# Sheet2.net
KiCad netlist of a schematic drawn in Altium Designer
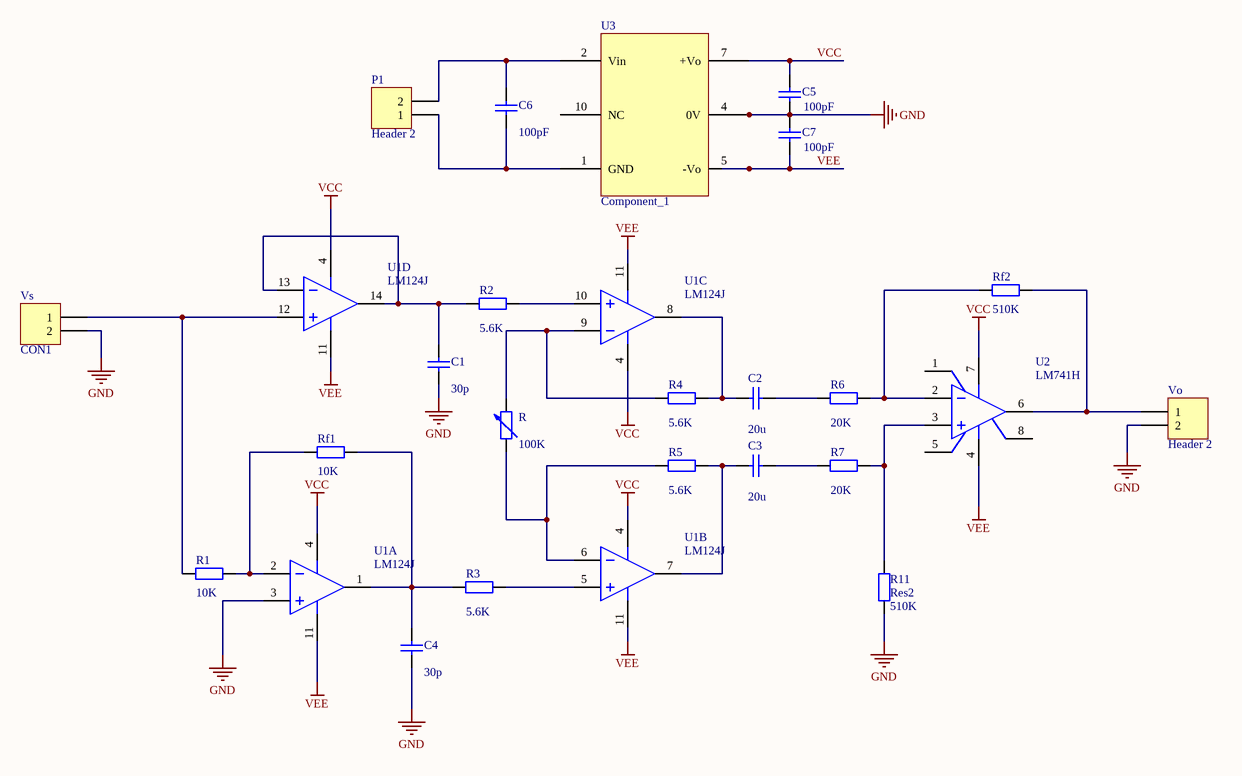
[diagram p0: Sheet2.SchDoc]

(export (version "E")
  (design (tool "Eeschema 10.0.6"))
  (components
    (comp (ref "C1")
      (value "30p")
      (footprint "RAD-0.3")
      (description "Capacitor")
      (fields (field (name "Comment") "Cap") (field (name "PUBLISHER") "Altium Limited"))
      (libsource (lib "Miscellaneous Devices") (part "Cap"))
    )
    (comp (ref "C2")
      (value "20u")
      (footprint "RAD-0.3")
      (description "Capacitor")
      (fields (field (name "Comment") "Cap") (field (name "PUBLISHER") "Altium Limited"))
      (libsource (lib "Miscellaneous Devices") (part "Cap"))
    )
    (comp (ref "C3")
      (value "20u")
      (footprint "RAD-0.3")
      (description "Capacitor")
      (fields (field (name "Comment") "Cap") (field (name "PUBLISHER") "Altium Limited"))
      (libsource (lib "Miscellaneous Devices") (part "Cap"))
    )
    (comp (ref "C4")
      (value "30p")
      (footprint "RAD-0.3")
      (description "Capacitor")
      (fields (field (name "Comment") "Cap") (field (name "PUBLISHER") "Altium Limited"))
      (libsource (lib "Miscellaneous Devices") (part "Cap"))
    )
    (comp (ref "C5")
      (value "100pF")
      (footprint "RAD-0.3")
      (description "Capacitor")
      (fields (field (name "Comment") "Cap") (field (name "PUBLISHER") "Altium Limited"))
      (libsource (lib "Miscellaneous Devices") (part "Cap"))
    )
    (comp (ref "C6")
      (value "100pF")
      (footprint "RAD-0.3")
      (description "Capacitor")
      (fields (field (name "Comment") "Cap") (field (name "PUBLISHER") "Altium Limited"))
      (libsource (lib "Miscellaneous Devices") (part "Cap"))
    )
    (comp (ref "C7")
      (value "100pF")
      (footprint "RAD-0.3")
      (description "Capacitor")
      (fields (field (name "Comment") "Cap") (field (name "PUBLISHER") "Altium Limited"))
      (libsource (lib "Miscellaneous Devices") (part "Cap"))
    )
    (comp (ref "P1")
      (value "Header 2")
      (footprint "HDR1X2")
      (description "Header, 2-Pin")
      (fields (field (name "PUBLISHER") "Altium Limited"))
      (libsource (lib "") (part "Header 2_2"))
    )
    (comp (ref "R")
      (value "100K")
      (footprint "AXIAL-0.6")
      (description "Variable Resistor")
      (fields (field (name "Comment") "Res Adj2") (field (name "PUBLISHER") "Altium Limited"))
      (libsource (lib "Miscellaneous Devices") (part "Res Adj2"))
    )
    (comp (ref "R1")
      (value "10K")
      (footprint "AXIAL-0.4")
      (description "Resistor")
      (fields (field (name "Comment") "Res2") (field (name "PUBLISHER") "Altium Limited"))
      (libsource (lib "") (part "Res2_1"))
    )
    (comp (ref "R2")
      (value "5.6K")
      (footprint "AXIAL-0.4")
      (description "Resistor")
      (fields (field (name "Comment") "Res2") (field (name "PUBLISHER") "Altium Limited"))
      (libsource (lib "") (part "Res2_1"))
    )
    (comp (ref "R3")
      (value "5.6K")
      (footprint "AXIAL-0.4")
      (description "Resistor")
      (fields (field (name "Comment") "Res2") (field (name "PUBLISHER") "Altium Limited"))
      (libsource (lib "") (part "Res2_1"))
    )
    (comp (ref "R4")
      (value "5.6K")
      (footprint "AXIAL-0.4")
      (description "Resistor")
      (fields (field (name "Comment") "Res2") (field (name "PUBLISHER") "Altium Limited"))
      (libsource (lib "") (part "Res2_1"))
    )
    (comp (ref "R5")
      (value "5.6K")
      (footprint "AXIAL-0.4")
      (description "Resistor")
      (fields (field (name "Comment") "Res2") (field (name "PUBLISHER") "Altium Limited"))
      (libsource (lib "") (part "Res2_1"))
    )
    (comp (ref "R6")
      (value "20K")
      (footprint "AXIAL-0.4")
      (description "Resistor")
      (fields (field (name "Comment") "Res2") (field (name "PUBLISHER") "Altium Limited"))
      (libsource (lib "") (part "Res2_1"))
    )
    (comp (ref "R7")
      (value "20K")
      (footprint "AXIAL-0.4")
      (description "Resistor")
      (fields (field (name "Comment") "Res2") (field (name "PUBLISHER") "Altium Limited"))
      (libsource (lib "") (part "Res2_1"))
    )
    (comp (ref "R11")
      (value "Res2")
      (footprint "AXIAL-0.4")
      (description "Resistor")
      (fields (field (name "ALTIUM_VALUE") "510K") (field (name "PUBLISHER") "Altium Limited"))
      (libsource (lib "") (part "Res2_2"))
    )
    (comp (ref "Rf1")
      (value "10K")
      (footprint "AXIAL-0.4")
      (description "Resistor")
      (fields (field (name "Comment") "Res2") (field (name "PUBLISHER") "Altium Limited"))
      (libsource (lib "") (part "Res2_1"))
    )
    (comp (ref "Rf2")
      (value "510K")
      (footprint "AXIAL-0.4")
      (description "Resistor")
      (fields (field (name "Comment") "Res2") (field (name "PUBLISHER") "Altium Limited"))
      (libsource (lib "Miscellaneous Devices") (part "Res2"))
    )
    (comp (ref "U1")
      (value "LM124J")
      (footprint "J14A")
      (description "Low Power Quad Operational Amplifier, 14-pin CerDIP")
      (fields
        (field (name "MANUFACTURER") "National Semiconductor")
        (field (name "PUBLISHER") "Altium Limited")
      )
      (libsource (lib "NSC Amplifier") (part "LM124J"))
    )
    (comp (ref "U2")
      (value "LM741H")
      (footprint "H08C")
      (description "Operational Amplifier, 8-pin TO-99")
      (fields
        (field (name "MANUFACTURER") "National Semiconductor")
        (field (name "PUBLISHER") "Altium Limited")
      )
      (libsource (lib "NSC Amplifier") (part "LM741H"))
    )
    (comp (ref "U3")
      (value "Component_1")
      (footprint "PCBComponent_1")
      (libsource (lib "Schlib1") (part "Component_1"))
    )
    (comp (ref "Vo")
      (value "Header 2")
      (footprint "HDR1X2")
      (description "Header, 2-Pin")
      (fields (field (name "PUBLISHER") "Altium Limited"))
      (libsource (lib "") (part "Header 2_1"))
    )
    (comp (ref "Vs")
      (value "CON1")
      (footprint "HDR1X2")
      (description "Header, 2-Pin")
      (fields (field (name "PUBLISHER") "Altium Limited"))
      (libsource (lib "Miscellaneous Connectors") (part "Header 2"))
    )
  )
  (nets
    (net (code "1") (name "GND") (class "Default")
      (node (ref "C1") (pin "1") (pinfunction "1_1") (pintype "passive"))
      (node (ref "C4") (pin "1") (pinfunction "1_1") (pintype "passive"))
      (node (ref "C5") (pin "1") (pinfunction "1_1") (pintype "passive"))
      (node (ref "C7") (pin "2") (pinfunction "2_2") (pintype "passive"))
      (node (ref "R11") (pin "1") (pinfunction "1_1") (pintype "passive"))
      (node (ref "U1") (pin "3") (pinfunction "IN1+_3") (pintype "passive"))
      (node (ref "U3") (pin "4") (pinfunction "0V_4") (pintype "passive"))
      (node (ref "Vo") (pin "2") (pinfunction "2_2") (pintype "passive"))
      (node (ref "Vs") (pin "2") (pinfunction "2_2") (pintype "passive"))
    )
    (net (code "2") (name "Net-(C2-Pad2)") (class "Default")
      (node (ref "C2") (pin "2") (pinfunction "2_2") (pintype "passive"))
      (node (ref "R6") (pin "1") (pinfunction "1_1") (pintype "passive"))
    )
    (net (code "3") (name "Net-(C3-Pad2)") (class "Default")
      (node (ref "C3") (pin "2") (pinfunction "2_2") (pintype "passive"))
      (node (ref "R7") (pin "1") (pinfunction "1_1") (pintype "passive"))
    )
    (net (code "4") (name "Net-(U1A-IN1-)") (class "Default")
      (node (ref "R1") (pin "2") (pinfunction "2_2") (pintype "passive"))
      (node (ref "Rf1") (pin "1") (pinfunction "1_1") (pintype "passive"))
      (node (ref "U1") (pin "2") (pinfunction "IN1-_2") (pintype "passive"))
    )
    (net (code "5") (name "Net-(U1A-OUT1)") (class "Default")
      (node (ref "C4") (pin "2") (pinfunction "2_2") (pintype "passive"))
      (node (ref "R3") (pin "1") (pinfunction "1_1") (pintype "passive"))
      (node (ref "Rf1") (pin "2") (pinfunction "2_2") (pintype "passive"))
      (node (ref "U1") (pin "1") (pinfunction "OUT1_1") (pintype "passive"))
    )
    (net (code "6") (name "Net-(U1B-IN2+)") (class "Default")
      (node (ref "R3") (pin "2") (pinfunction "2_2") (pintype "passive"))
      (node (ref "U1") (pin "5") (pinfunction "IN2+_5") (pintype "input"))
    )
    (net (code "7") (name "Net-(U1B-IN2-)") (class "Default")
      (node (ref "R") (pin "1") (pinfunction "1_1") (pintype "passive"))
      (node (ref "R5") (pin "1") (pinfunction "1_1") (pintype "passive"))
      (node (ref "U1") (pin "6") (pinfunction "IN2-_6") (pintype "input"))
    )
    (net (code "8") (name "Net-(U1B-OUT2)") (class "Default")
      (node (ref "C3") (pin "1") (pinfunction "1_1") (pintype "passive"))
      (node (ref "R5") (pin "2") (pinfunction "2_2") (pintype "passive"))
      (node (ref "U1") (pin "7") (pinfunction "OUT2_7") (pintype "output"))
    )
    (net (code "9") (name "Net-(U1C-IN3+)") (class "Default")
      (node (ref "R2") (pin "2") (pinfunction "2_2") (pintype "passive"))
      (node (ref "U1") (pin "10") (pinfunction "IN3+_10") (pintype "input"))
    )
    (net (code "10") (name "Net-(U1C-IN3-)") (class "Default")
      (node (ref "R") (pin "2") (pinfunction "2_2") (pintype "passive"))
      (node (ref "R4") (pin "1") (pinfunction "1_1") (pintype "passive"))
      (node (ref "U1") (pin "9") (pinfunction "IN3-_9") (pintype "input"))
    )
    (net (code "11") (name "Net-(U1C-OUT3)") (class "Default")
      (node (ref "C2") (pin "1") (pinfunction "1_1") (pintype "passive"))
      (node (ref "R4") (pin "2") (pinfunction "2_2") (pintype "passive"))
      (node (ref "U1") (pin "8") (pinfunction "OUT3_8") (pintype "output"))
    )
    (net (code "12") (name "Net-(U1D-IN4+)") (class "Default")
      (node (ref "R1") (pin "1") (pinfunction "1_1") (pintype "passive"))
      (node (ref "U1") (pin "12") (pinfunction "IN4+_12") (pintype "input"))
      (node (ref "Vs") (pin "1") (pinfunction "1_1") (pintype "passive"))
    )
    (net (code "13") (name "Net-(U1D-IN4-)") (class "Default")
      (node (ref "C1") (pin "2") (pinfunction "2_2") (pintype "passive"))
      (node (ref "R2") (pin "1") (pinfunction "1_1") (pintype "passive"))
      (node (ref "U1") (pin "13") (pinfunction "IN4-_13") (pintype "input"))
      (node (ref "U1") (pin "14") (pinfunction "OUT4_14") (pintype "output"))
    )
    (net (code "14") (name "Net-(U2-IN+)") (class "Default")
      (node (ref "R11") (pin "2") (pinfunction "2_2") (pintype "passive"))
      (node (ref "R7") (pin "2") (pinfunction "2_2") (pintype "passive"))
      (node (ref "U2") (pin "3") (pinfunction "IN+_3") (pintype "passive"))
    )
    (net (code "15") (name "Net-(U2-IN-)") (class "Default")
      (node (ref "R6") (pin "2") (pinfunction "2_2") (pintype "passive"))
      (node (ref "Rf2") (pin "2") (pinfunction "2_2") (pintype "passive"))
      (node (ref "U2") (pin "2") (pinfunction "IN-_2") (pintype "passive"))
    )
    (net (code "16") (name "Net-(U2-OUT)") (class "Default")
      (node (ref "Rf2") (pin "1") (pinfunction "1_1") (pintype "passive"))
      (node (ref "U2") (pin "6") (pinfunction "OUT_6") (pintype "passive"))
      (node (ref "Vo") (pin "1") (pinfunction "1_1") (pintype "passive"))
    )
    (net (code "17") (name "Net-(U3-GND)") (class "Default")
      (node (ref "C6") (pin "1") (pinfunction "1_1") (pintype "passive"))
      (node (ref "P1") (pin "1") (pinfunction "1_1") (pintype "passive"))
      (node (ref "U3") (pin "1") (pinfunction "GND_1") (pintype "power_in"))
    )
    (net (code "18") (name "Net-(U3-Vin)") (class "Default")
      (node (ref "C6") (pin "2") (pinfunction "2_2") (pintype "passive"))
      (node (ref "P1") (pin "2") (pinfunction "2_2") (pintype "passive"))
      (node (ref "U3") (pin "2") (pinfunction "Vin_2") (pintype "power_in"))
    )
    (net (code "19") (name "VCC") (class "Default")
      (node (ref "C5") (pin "2") (pinfunction "2_2") (pintype "passive"))
      (node (ref "U1") (pin "4") (pinfunction "V+_4") (pintype "power_in"))
      (node (ref "U2") (pin "7") (pinfunction "V+_7") (pintype "power_in"))
      (node (ref "U3") (pin "7") (pinfunction "+Vo_7") (pintype "passive"))
    )
    (net (code "20") (name "VEE") (class "Default")
      (node (ref "C7") (pin "1") (pinfunction "1_1") (pintype "passive"))
      (node (ref "U1") (pin "11") (pinfunction "GND_11") (pintype "power_in"))
      (node (ref "U2") (pin "4") (pinfunction "V-_4") (pintype "power_in"))
      (node (ref "U3") (pin "5") (pinfunction "-Vo_5") (pintype "power_in"))
    )
    (net (code "21") (name "unconnected-(U2-NC-Pad8)") (class "Default")
      (node (ref "U2") (pin "8") (pinfunction "NC_8") (pintype "passive"))
    )
    (net (code "22") (name "unconnected-(U2-OFS_NULL-Pad1)") (class "Default")
      (node (ref "U2") (pin "1") (pinfunction "OFS_NULL_1") (pintype "passive"))
    )
    (net (code "23") (name "unconnected-(U2-OFS_NULL-Pad5)") (class "Default")
      (node (ref "U2") (pin "5") (pinfunction "OFS_NULL_5") (pintype "passive"))
    )
    (net (code "24") (name "unconnected-(U3-NC-Pad10)") (class "Default")
      (node (ref "U3") (pin "10") (pinfunction "NC_10") (pintype "passive"))
    )
  )
)
